# TypeC_2_54.net
KiCad netlist of a schematic drawn in Altium Designer
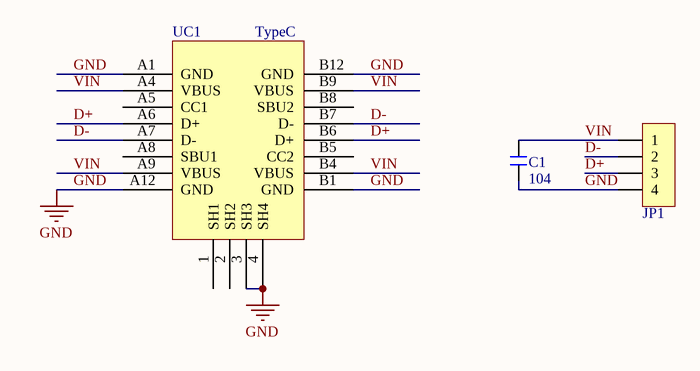
[diagram p0: TypeC_2.54.SchDoc]

(export (version "E")
  (design (tool "Eeschema 10.0.6"))
  (components
    (comp (ref "C1")
      (value "104")
      (footprint "C 0603_L")
      (description "无极性贴片电容")
      (fields (field (name "版权归属") "源创客"))
      (libsource (lib "3.1   - 电阻-电容-电感") (part "C"))
    )
    (comp (ref "JP1")
      (value "HDR-1X4")
      (footprint "HDR2.54-LI-4P")
      (description "4P接插件")
      (fields (field (name "版权归属") "源创客"))
      (libsource (lib "4.6   - 接插件-脚距2.54") (part "Header 4"))
    )
    (comp (ref "UC1")
      (value "TypeC")
      (footprint "Type-C_8.64.5.82.12pin")
      (description "TypeC_SinglePin_Short")
      (libsource (lib "My Library") (part "USB_Type-C"))
    )
  )
  (nets
    (net (code "1") (name "/D+") (class "Default")
      (node (ref "JP1") (pin "3") (pinfunction "3_3") (pintype "passive"))
      (node (ref "UC1") (pin "A6") (pinfunction "D+_A6") (pintype "passive"))
      (node (ref "UC1") (pin "B6") (pinfunction "D+_B6") (pintype "passive"))
    )
    (net (code "2") (name "/D-") (class "Default")
      (node (ref "JP1") (pin "2") (pinfunction "2_2") (pintype "passive"))
      (node (ref "UC1") (pin "A7") (pinfunction "D-_A7") (pintype "passive"))
      (node (ref "UC1") (pin "B7") (pinfunction "D-_B7") (pintype "passive"))
    )
    (net (code "3") (name "/VIN") (class "Default")
      (node (ref "C1") (pin "2") (pinfunction "2_2") (pintype "passive"))
      (node (ref "JP1") (pin "1") (pinfunction "1_1") (pintype "passive"))
      (node (ref "UC1") (pin "A4") (pinfunction "VBUS_A4") (pintype "passive"))
      (node (ref "UC1") (pin "A9") (pinfunction "VBUS_A9") (pintype "passive"))
      (node (ref "UC1") (pin "B4") (pinfunction "VBUS_B4") (pintype "passive"))
      (node (ref "UC1") (pin "B9") (pinfunction "VBUS_B9") (pintype "passive"))
    )
    (net (code "4") (name "GND") (class "Default")
      (node (ref "C1") (pin "1") (pinfunction "1_1") (pintype "passive"))
      (node (ref "JP1") (pin "4") (pinfunction "4_4") (pintype "passive"))
      (node (ref "UC1") (pin "3") (pinfunction "SH3_3") (pintype "passive"))
      (node (ref "UC1") (pin "4") (pinfunction "SH4_4") (pintype "passive"))
      (node (ref "UC1") (pin "A1") (pinfunction "GND_A1") (pintype "passive"))
      (node (ref "UC1") (pin "A12") (pinfunction "GND_A12") (pintype "passive"))
      (node (ref "UC1") (pin "B1") (pinfunction "GND_B1") (pintype "passive"))
      (node (ref "UC1") (pin "B12") (pinfunction "GND_B12") (pintype "passive"))
    )
    (net (code "5") (name "unconnected-(UC1-CC1-PadA5)") (class "Default")
      (node (ref "UC1") (pin "A5") (pinfunction "CC1_A5") (pintype "passive"))
    )
    (net (code "6") (name "unconnected-(UC1-CC2-PadB5)") (class "Default")
      (node (ref "UC1") (pin "B5") (pinfunction "CC2_B5") (pintype "passive"))
    )
    (net (code "7") (name "unconnected-(UC1-SBU1-PadA8)") (class "Default")
      (node (ref "UC1") (pin "A8") (pinfunction "SBU1_A8") (pintype "passive"))
    )
    (net (code "8") (name "unconnected-(UC1-SBU2-PadB8)") (class "Default")
      (node (ref "UC1") (pin "B8") (pinfunction "SBU2_B8") (pintype "passive"))
    )
    (net (code "9") (name "unconnected-(UC1-SH1-Pad1)") (class "Default")
      (node (ref "UC1") (pin "1") (pinfunction "SH1_1") (pintype "passive"))
    )
    (net (code "10") (name "unconnected-(UC1-SH2-Pad2)") (class "Default")
      (node (ref "UC1") (pin "2") (pinfunction "SH2_2") (pintype "passive"))
    )
  )
)
